# Motor.net
KiCad netlist of a schematic drawn in Altium Designer
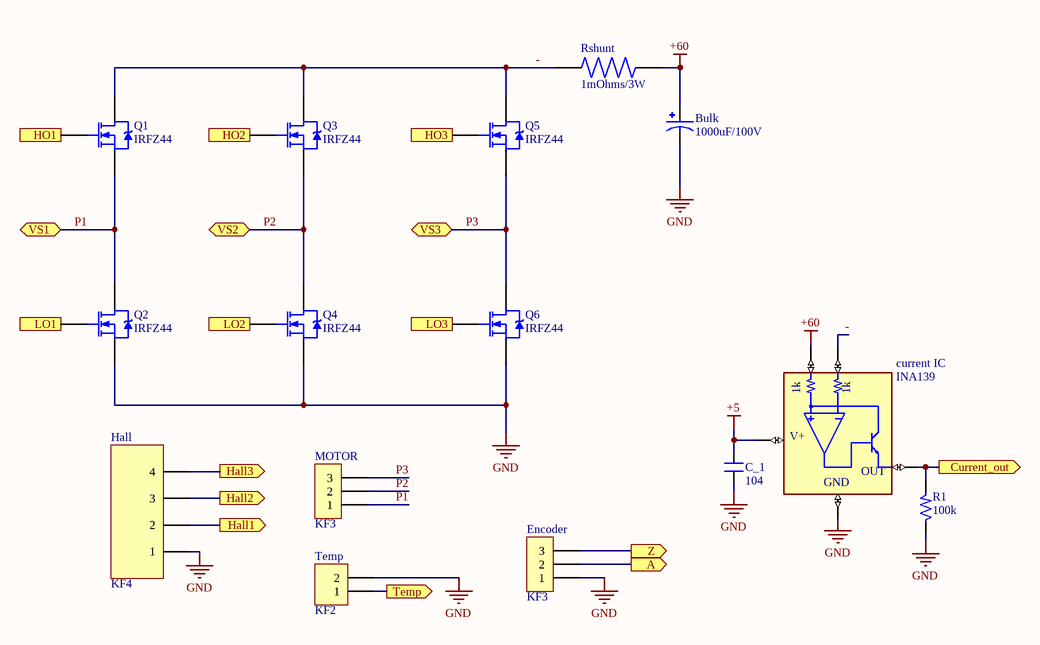
[diagram p0: Motor.SchDoc]

(export (version "E")
  (design (tool "Eeschema 10.0.6"))
  (components
    (comp (ref "Bulk")
      (value "1000uF/100V")
      (footprint "CAPPRD750W80D1800H3550")
      (description "Aluminum Electrolytic Capacitors, NHG-A Series, 1000uF +/- 20%, 100V, Radial lead type(18x35.5mm)")
      (fields (field (name "MF") "Panasonic") (field (name "MP") "ECA-2AHG102E"))
      (libsource (lib "1000uF_100V") (part "ECA2AHG102E"))
    )
    (comp (ref "current IC")
      (value "INA139")
      (footprint "MICROCHIP SOT-23-5 OT")
      (description "Current Monitor Regulator High-Side SOT-23-5")
      (fields (field (name "MF") "Texas Instruments"))
      (libsource (lib "INA139") (part "INA139"))
    )
    (comp (ref "C_1")
      (value "104")
      (footprint "CAP FILM 0603_1608")
      (fields (field (name "DESIGNED BY") "VanDungEvn"))
      (libsource (lib "echipkool-com-library") (part "CN"))
    )
    (comp (ref "Encoder")
      (value "KF3")
      (footprint "KF3-5.08")
      (fields
        (field (name "MANUFACTURER") "Würth Elektronik eiSos GmbH")
        (field (name "PARTNO") "691103110003")
        (field (name "CREATED BY") "Karrer Zheng")
      )
      (libsource (lib "LIBRARYALT") (part "KF3"))
    )
    (comp (ref "Hall")
      (value "KF4")
      (footprint "KF4-5.08")
      (fields
        (field (name "MANUFACTURER") "Würth Elektronik eiSos GmbH")
        (field (name "PARTNO") "691133710004")
        (field (name "CREATED BY") "Baojun Chen")
      )
      (libsource (lib "LIBRARYALT") (part "KF4"))
    )
    (comp (ref "MOTOR")
      (value "KF3")
      (footprint "KF3-5.08")
      (fields
        (field (name "MANUFACTURER") "Würth Elektronik eiSos GmbH")
        (field (name "PARTNO") "691103110003")
        (field (name "CREATED BY") "Karrer Zheng")
      )
      (libsource (lib "LIBRARYALT") (part "KF3"))
    )
    (comp (ref "Q1")
      (value "IRFZ44")
      (footprint "DPAK508P1524X483-3N")
      (description "HEXFET N-Channel Power MOSFET")
      (libsource (lib "echipkool-com-library") (part "IRFZ44"))
    )
    (comp (ref "Q2")
      (value "IRFZ44")
      (footprint "DPAK508P1524X483-3N")
      (description "HEXFET N-Channel Power MOSFET")
      (libsource (lib "echipkool-com-library") (part "IRFZ44"))
    )
    (comp (ref "Q3")
      (value "IRFZ44")
      (footprint "DPAK508P1524X483-3N")
      (description "HEXFET N-Channel Power MOSFET")
      (libsource (lib "echipkool-com-library") (part "IRFZ44"))
    )
    (comp (ref "Q4")
      (value "IRFZ44")
      (footprint "DPAK508P1524X483-3N")
      (description "HEXFET N-Channel Power MOSFET")
      (libsource (lib "echipkool-com-library") (part "IRFZ44"))
    )
    (comp (ref "Q5")
      (value "IRFZ44")
      (footprint "DPAK508P1524X483-3N")
      (description "HEXFET N-Channel Power MOSFET")
      (libsource (lib "echipkool-com-library") (part "IRFZ44"))
    )
    (comp (ref "Q6")
      (value "IRFZ44")
      (footprint "DPAK508P1524X483-3N")
      (description "HEXFET N-Channel Power MOSFET")
      (libsource (lib "echipkool-com-library") (part "IRFZ44"))
    )
    (comp (ref "R1")
      (value "100k")
      (footprint "RES 0603_1608")
      (description "Resistor 1/4W")
      (libsource (lib "echipkool-com-library") (part "R"))
    )
    (comp (ref "Rshunt")
      (value "1mOhms/3W")
      (footprint "RESM11569X253N")
      (fields (field (name "MP") "WSR31L000FEA"))
      (libsource (lib "WSR31L000FEA") (part "WSR31L000FEA"))
    )
    (comp (ref "Temp")
      (value "KF2")
      (footprint "KF2-5.08")
      (fields
        (field (name "MANUFACTURER") "Würth Elektronik eiSos GmbH")
        (field (name "PARTNO") "691103110002")
        (field (name "CREATED BY") "Karrer Zheng")
      )
      (libsource (lib "LIBRARYALT") (part "KF2"))
    )
  )
  (nets
    (net (code "1") (name "+5") (class "Default")
      (node (ref "C_1") (pin "1") (pinfunction "1_1") (pintype "passive"))
      (node (ref "current IC") (pin "5") (pinfunction "V+_5") (pintype "bidirectional"))
    )
    (net (code "2") (name "+60") (class "Default")
      (node (ref "Bulk") (pin "P") (pinfunction "P_P") (pintype "passive"))
      (node (ref "Rshunt") (pin "2") (pinfunction "2_2") (pintype "passive"))
      (node (ref "current IC") (pin "3") (pinfunction "VIN+_3") (pintype "bidirectional"))
    )
    (net (code "3") (name "/-") (class "Default")
      (node (ref "Q1") (pin "2") (pinfunction "D_2") (pintype "passive"))
      (node (ref "Q3") (pin "2") (pinfunction "D_2") (pintype "passive"))
      (node (ref "Q5") (pin "2") (pinfunction "D_2") (pintype "passive"))
      (node (ref "Rshunt") (pin "1") (pinfunction "1_1") (pintype "passive"))
      (node (ref "current IC") (pin "4") (pinfunction "VIN-_4") (pintype "bidirectional"))
    )
    (net (code "4") (name "/A") (class "Default")
      (node (ref "Encoder") (pin "2") (pinfunction "2_2") (pintype "passive"))
    )
    (net (code "5") (name "/Current_out") (class "Default")
      (node (ref "R1") (pin "2") (pinfunction "2_2") (pintype "passive"))
      (node (ref "current IC") (pin "1") (pinfunction "OUT_1") (pintype "bidirectional"))
    )
    (net (code "6") (name "/HO1") (class "Default")
      (node (ref "Q1") (pin "1") (pinfunction "G_1") (pintype "passive"))
    )
    (net (code "7") (name "/HO2") (class "Default")
      (node (ref "Q3") (pin "1") (pinfunction "G_1") (pintype "passive"))
    )
    (net (code "8") (name "/HO3") (class "Default")
      (node (ref "Q5") (pin "1") (pinfunction "G_1") (pintype "passive"))
    )
    (net (code "9") (name "/Hall1") (class "Default")
      (node (ref "Hall") (pin "2") (pinfunction "2_2") (pintype "passive"))
    )
    (net (code "10") (name "/Hall2") (class "Default")
      (node (ref "Hall") (pin "3") (pinfunction "3_3") (pintype "passive"))
    )
    (net (code "11") (name "/Hall3") (class "Default")
      (node (ref "Hall") (pin "4") (pinfunction "4_4") (pintype "passive"))
    )
    (net (code "12") (name "/LO1") (class "Default")
      (node (ref "Q2") (pin "1") (pinfunction "G_1") (pintype "passive"))
    )
    (net (code "13") (name "/LO2") (class "Default")
      (node (ref "Q4") (pin "1") (pinfunction "G_1") (pintype "passive"))
    )
    (net (code "14") (name "/LO3") (class "Default")
      (node (ref "Q6") (pin "1") (pinfunction "G_1") (pintype "passive"))
    )
    (net (code "15") (name "/P1") (class "Default")
      (node (ref "MOTOR") (pin "1") (pinfunction "1_1") (pintype "passive"))
      (node (ref "Q1") (pin "3") (pinfunction "S_3") (pintype "passive"))
      (node (ref "Q2") (pin "2") (pinfunction "D_2") (pintype "passive"))
    )
    (net (code "16") (name "/P2") (class "Default")
      (node (ref "MOTOR") (pin "2") (pinfunction "2_2") (pintype "passive"))
      (node (ref "Q3") (pin "3") (pinfunction "S_3") (pintype "passive"))
      (node (ref "Q4") (pin "2") (pinfunction "D_2") (pintype "passive"))
    )
    (net (code "17") (name "/P3") (class "Default")
      (node (ref "MOTOR") (pin "3") (pinfunction "3_3") (pintype "passive"))
      (node (ref "Q5") (pin "3") (pinfunction "S_3") (pintype "passive"))
      (node (ref "Q6") (pin "2") (pinfunction "D_2") (pintype "passive"))
    )
    (net (code "18") (name "/Temp") (class "Default")
      (node (ref "Temp") (pin "1") (pinfunction "1_1") (pintype "passive"))
    )
    (net (code "19") (name "/Z") (class "Default")
      (node (ref "Encoder") (pin "3") (pinfunction "3_3") (pintype "passive"))
    )
    (net (code "20") (name "GND") (class "Default")
      (node (ref "Bulk") (pin "N") (pinfunction "N_N") (pintype "passive"))
      (node (ref "C_1") (pin "2") (pinfunction "2_2") (pintype "passive"))
      (node (ref "Encoder") (pin "1") (pinfunction "1_1") (pintype "passive"))
      (node (ref "Hall") (pin "1") (pinfunction "1_1") (pintype "passive"))
      (node (ref "Q2") (pin "3") (pinfunction "S_3") (pintype "passive"))
      (node (ref "Q4") (pin "3") (pinfunction "S_3") (pintype "passive"))
      (node (ref "Q6") (pin "3") (pinfunction "S_3") (pintype "passive"))
      (node (ref "R1") (pin "1") (pinfunction "1_1") (pintype "passive"))
      (node (ref "Temp") (pin "2") (pinfunction "2_2") (pintype "passive"))
      (node (ref "current IC") (pin "2") (pinfunction "GND_2") (pintype "bidirectional"))
    )
  )
)
